# ZenithController.net
KiCad netlist of a schematic drawn in EAGLE
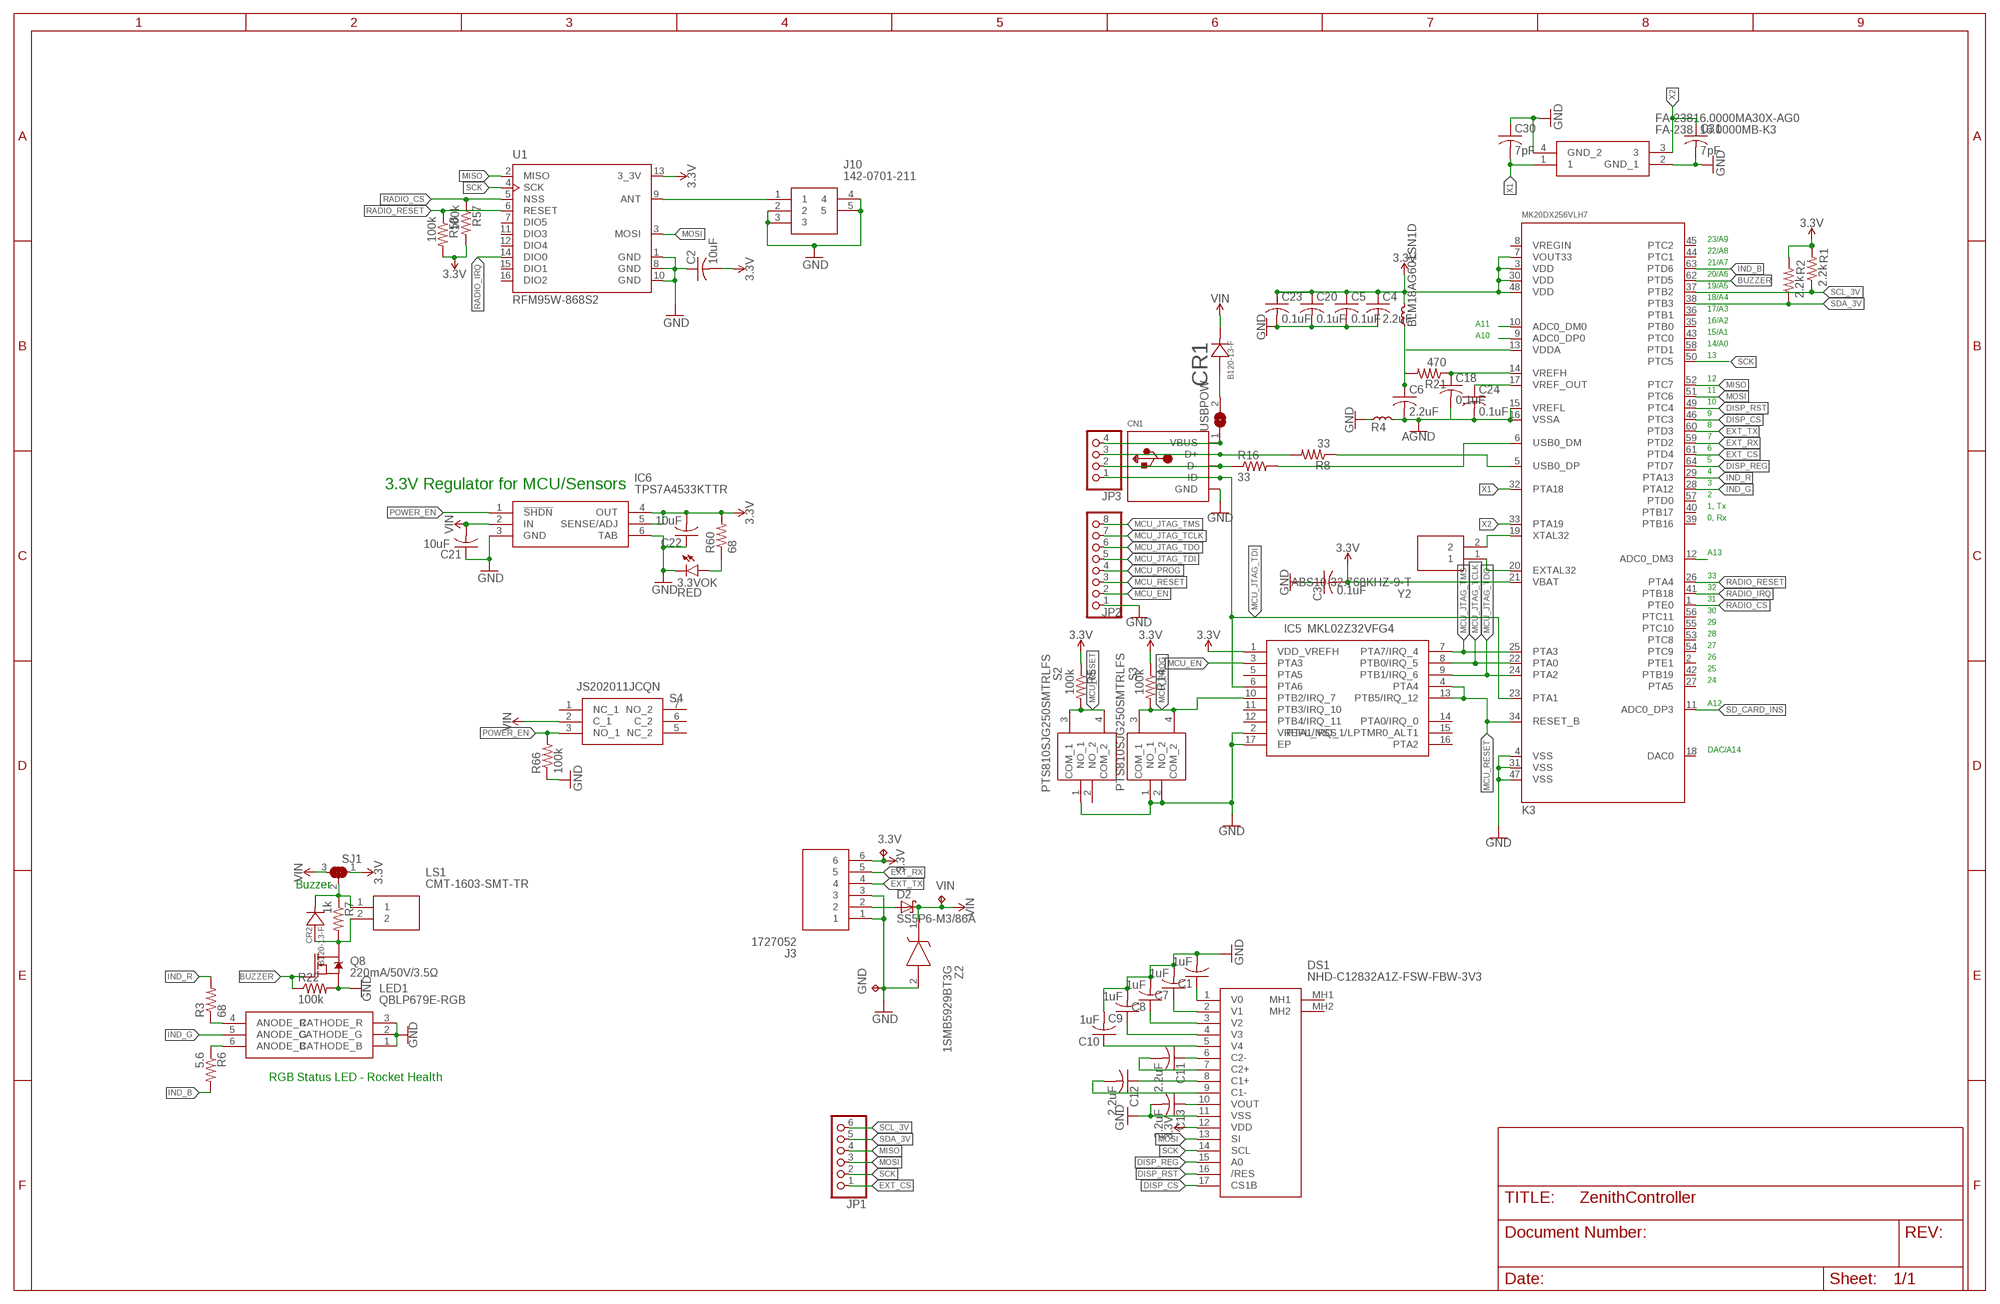
[diagram p0: schematic, sheet 1]

(export (version "E")
  (design (tool "Eeschema 10.0.6"))
  (components
    (comp (ref "3.3V")
      (value "TPB1,27")
      (footprint "eagle-import:B1,27")
      (libsource (lib "eagle-import") (part "TPB1,27"))
    )
    (comp (ref "3.3VOK")
      (value "RED")
      (footprint "eagle-import:CHIP-LED0805")
      (libsource (lib "eagle-import") (part "LEDCHIP-LED0805"))
    )
    (comp (ref "BLM18AG601SN1D")
      (value "FERRITE")
      (footprint "eagle-import:L0603")
      (fields (field (name "MF") "Murata Electronics") (field (name "MPN") " BLM18AG601SN1D"))
      (libsource (lib "eagle-import") (part "FERRITE"))
    )
    (comp (ref "C1")
      (value "1uF")
      (footprint "eagle-import:C0603")
      (libsource (lib "eagle-import") (part "C-USC0603"))
    )
    (comp (ref "C2")
      (value "10uF")
      (footprint "eagle-import:C0603")
      (libsource (lib "eagle-import") (part "C-USC0603"))
    )
    (comp (ref "C3")
      (value "0.1uF")
      (footprint "eagle-import:C0603")
      (libsource (lib "eagle-import") (part "C-USC0603"))
    )
    (comp (ref "C4")
      (value "2.2uF")
      (footprint "eagle-import:C0603")
      (libsource (lib "eagle-import") (part "C-USC0603"))
    )
    (comp (ref "C5")
      (value "0.1uF")
      (footprint "eagle-import:C0603")
      (libsource (lib "eagle-import") (part "C-USC0603"))
    )
    (comp (ref "C6")
      (value "2.2uF")
      (footprint "eagle-import:C0603")
      (libsource (lib "eagle-import") (part "C-USC0603"))
    )
    (comp (ref "C7")
      (value "1uF")
      (footprint "eagle-import:C0603")
      (libsource (lib "eagle-import") (part "C-USC0603"))
    )
    (comp (ref "C8")
      (value "1uF")
      (footprint "eagle-import:C0603")
      (libsource (lib "eagle-import") (part "C-USC0603"))
    )
    (comp (ref "C9")
      (value "1uF")
      (footprint "eagle-import:C0603")
      (libsource (lib "eagle-import") (part "C-USC0603"))
    )
    (comp (ref "C10")
      (value "1uF")
      (footprint "eagle-import:C0603")
      (libsource (lib "eagle-import") (part "C-USC0603"))
    )
    (comp (ref "C11")
      (value "2.2uF")
      (footprint "eagle-import:C0603")
      (libsource (lib "eagle-import") (part "C-USC0603"))
    )
    (comp (ref "C12")
      (value "2.2uF")
      (footprint "eagle-import:C0603")
      (libsource (lib "eagle-import") (part "C-USC0603"))
    )
    (comp (ref "C13")
      (value "2.2uF")
      (footprint "eagle-import:C0603")
      (libsource (lib "eagle-import") (part "C-USC0603"))
    )
    (comp (ref "C18")
      (value "0.1uF")
      (footprint "eagle-import:C0603")
      (libsource (lib "eagle-import") (part "C-USC0603"))
    )
    (comp (ref "C20")
      (value "0.1uF")
      (footprint "eagle-import:C0603")
      (libsource (lib "eagle-import") (part "C-USC0603"))
    )
    (comp (ref "C21")
      (value "10uF")
      (footprint "eagle-import:C0603")
      (libsource (lib "eagle-import") (part "C-USC0603"))
    )
    (comp (ref "C22")
      (value "10uF")
      (footprint "eagle-import:C0603")
      (libsource (lib "eagle-import") (part "C-USC0603"))
    )
    (comp (ref "C23")
      (value "0.1uF")
      (footprint "eagle-import:C0603")
      (libsource (lib "eagle-import") (part "C-USC0603"))
    )
    (comp (ref "C24")
      (value "0.1uF")
      (footprint "eagle-import:C0603")
      (libsource (lib "eagle-import") (part "C-USC0603"))
    )
    (comp (ref "C30")
      (value "7pF")
      (footprint "eagle-import:C0603")
      (libsource (lib "eagle-import") (part "C-USC0603"))
    )
    (comp (ref "C31")
      (value "7pF")
      (footprint "eagle-import:C0603")
      (libsource (lib "eagle-import") (part "C-USC0603"))
    )
    (comp (ref "CN1")
      (value "USBMINIB")
      (footprint "eagle-import:USB-MINIB")
      (libsource (lib "eagle-import") (part "USBMINIB"))
    )
    (comp (ref "CR1")
      (value "B120-13-F")
      (footprint "eagle-import:SMA_DIO")
      (libsource (lib "eagle-import") (part "B120-13-F"))
    )
    (comp (ref "CR2")
      (value "B120-13-F")
      (footprint "eagle-import:SMA_DIO")
      (libsource (lib "eagle-import") (part "B120-13-F"))
    )
    (comp (ref "D2")
      (value "SS5P6-M3/86A")
      (footprint "eagle-import:TO-277A(SMPC)")
      (fields (field (name "MF") "Vishay Semiconductor"))
      (libsource (lib "eagle-import") (part "SS5P6-M3/86A"))
    )
    (comp (ref "DS1")
      (value "NHD-C12832A1Z-FSW-FBW-3V3")
      (footprint "eagle-import:NHDC12832A1ZFSWFBW3V3")
      (fields (field (name "MOUSER_PART_NUMBER") "763-C12832A1ZFSWFBW3"))
      (libsource (lib "eagle-import") (part "NHD-C12832A1Z-FSW-FBW-3V3"))
    )
    (comp (ref "FA-23816.0000MA30X-AG0")
      (value "FA-238_16.0000MB-K3")
      (footprint "eagle-import:EPSON-FA-238")
      (fields
        (field (name "ARROW_PART_NUMBER") "FA-238 16.0000MB-K3")
        (field (name "MOUSER_PART_NUMBER") "732-FA238-16B-K3")
      )
      (libsource (lib "eagle-import") (part "FA-238_16.0000MB-K3"))
    )
    (comp (ref "GND")
      (value "TPB1,27")
      (footprint "eagle-import:B1,27")
      (libsource (lib "eagle-import") (part "TPB1,27"))
    )
    (comp (ref "IC5")
      (value "MKL02Z32VFG4")
      (footprint "eagle-import:QFN50P300X300X65-17N")
      (fields (field (name "MOUSER_PART_NUMBER") "841-MKL02Z32VFG4"))
      (libsource (lib "eagle-import") (part "MKL02Z32VFG4"))
    )
    (comp (ref "IC6")
      (value "TPS7A4533KTTR")
      (footprint "eagle-import:KTT0005B")
      (fields (field (name "MOUSER_PART_NUMBER") "595-TPS7A4533KTTR"))
      (libsource (lib "eagle-import") (part "TPS7A4533KTTR"))
    )
    (comp (ref "J3")
      (value "1727052")
      (footprint "eagle-import:SHDR6W105P0X381_1X6_2285X730X8")
      (fields (field (name "MOUSER_PART_NUMBER") "651-1727052"))
      (libsource (lib "eagle-import") (part "1727052"))
    )
    (comp (ref "J10")
      (value "142-0701-211")
      (footprint "eagle-import:1420701211")
      (fields (field (name "MOUSER_PART_NUMBER") "530-1420701211"))
      (libsource (lib "eagle-import") (part "142-0701-211"))
    )
    (comp (ref "JP1")
      (value "PINHD-1X6")
      (footprint "eagle-import:1X06")
      (libsource (lib "eagle-import") (part "PINHD-1X6"))
    )
    (comp (ref "JP2")
      (value "PINHD-1X8")
      (footprint "eagle-import:1X08")
      (libsource (lib "eagle-import") (part "PINHD-1X8"))
    )
    (comp (ref "JP3")
      (value "PINHD-1X4")
      (footprint "eagle-import:1X04")
      (libsource (lib "eagle-import") (part "PINHD-1X4"))
    )
    (comp (ref "K3")
      (value "MK20DX256VLH7")
      (footprint "eagle-import:LQFP64-05")
      (fields (field (name "MF") "NXP"))
      (libsource (lib "eagle-import") (part "MK20DX256VLH7"))
    )
    (comp (ref "LED1")
      (value "QBLP679E-RGB")
      (footprint "eagle-import:QBLP679ERGB")
      (libsource (lib "eagle-import") (part "QBLP679E-RGB"))
    )
    (comp (ref "LS1")
      (value "CMT-1603-SMT-TR")
      (footprint "eagle-import:CMT1603SMTTR")
      (fields (field (name "MOUSER_PART_NUMBER") "490-CMT-1603-SMT-TR"))
      (libsource (lib "eagle-import") (part "CMT-1603-SMT-TR"))
    )
    (comp (ref "Q8")
      (value "220mA/50V/3.5Ω")
      (footprint "eagle-import:SOT23-3")
      (libsource (lib "eagle-import") (part "MOSFET-NCH-BSS138"))
    )
    (comp (ref "R1")
      (value "2.2k")
      (footprint "eagle-import:R0603")
      (libsource (lib "eagle-import") (part "R-US_R0603"))
    )
    (comp (ref "R2")
      (value "2.2k")
      (footprint "eagle-import:R0603")
      (libsource (lib "eagle-import") (part "R-US_R0603"))
    )
    (comp (ref "R3")
      (value "68")
      (footprint "eagle-import:R0603")
      (libsource (lib "eagle-import") (part "R-US_R0603"))
    )
    (comp (ref "R4")
      (value "FERRITE")
      (footprint "eagle-import:L0603")
      (fields (field (name "MF") "Murata Electronics") (field (name "MPN") " BLM18AG601SN1D"))
      (libsource (lib "eagle-import") (part "FERRITE"))
    )
    (comp (ref "R5")
      (value "100k")
      (footprint "eagle-import:R0603")
      (libsource (lib "eagle-import") (part "R-US_R0603"))
    )
    (comp (ref "R6")
      (value "5.6")
      (footprint "eagle-import:R0603")
      (libsource (lib "eagle-import") (part "R-US_R0603"))
    )
    (comp (ref "R7")
      (value "1k")
      (footprint "eagle-import:R0603")
      (libsource (lib "eagle-import") (part "R-US_R0603"))
    )
    (comp (ref "R8")
      (value "33")
      (footprint "eagle-import:R0603")
      (libsource (lib "eagle-import") (part "R-US_R0603"))
    )
    (comp (ref "R14")
      (value "100k")
      (footprint "eagle-import:R0603")
      (libsource (lib "eagle-import") (part "R-US_R0603"))
    )
    (comp (ref "R16")
      (value "33")
      (footprint "eagle-import:R0603")
      (libsource (lib "eagle-import") (part "R-US_R0603"))
    )
    (comp (ref "R21")
      (value "470")
      (footprint "eagle-import:R0603")
      (libsource (lib "eagle-import") (part "R-US_R0603"))
    )
    (comp (ref "R22")
      (value "100k")
      (footprint "eagle-import:R0603")
      (libsource (lib "eagle-import") (part "R-US_R0603"))
    )
    (comp (ref "R57")
      (value "100k")
      (footprint "eagle-import:R0603")
      (libsource (lib "eagle-import") (part "R-US_R0603"))
    )
    (comp (ref "R58")
      (value "100k")
      (footprint "eagle-import:R0603")
      (libsource (lib "eagle-import") (part "R-US_R0603"))
    )
    (comp (ref "R60")
      (value "68")
      (footprint "eagle-import:R0603")
      (libsource (lib "eagle-import") (part "R-US_R0603"))
    )
    (comp (ref "R66")
      (value "100k")
      (footprint "eagle-import:R0603")
      (libsource (lib "eagle-import") (part "R-US_R0603"))
    )
    (comp (ref "S2")
      (value "PTS810SJG250SMTRLFS")
      (footprint "eagle-import:PTS810SJG250SMTRLFS")
      (fields (field (name "MOUSER_PART_NUMBER") "611-PTS810SJG250SMTR"))
      (libsource (lib "eagle-import") (part "PTS810SJG250SMTRLFS"))
    )
    (comp (ref "S3")
      (value "PTS810SJG250SMTRLFS")
      (footprint "eagle-import:PTS810SJG250SMTRLFS")
      (fields (field (name "MOUSER_PART_NUMBER") "611-PTS810SJG250SMTR"))
      (libsource (lib "eagle-import") (part "PTS810SJG250SMTRLFS"))
    )
    (comp (ref "S4")
      (value "JS202011JCQN")
      (footprint "eagle-import:JS202011JCQN")
      (fields (field (name "MOUSER_PART_NUMBER") "611-JS202011JCQN"))
      (libsource (lib "eagle-import") (part "JS202011JCQN"))
    )
    (comp (ref "SJ1")
      (value "SOLDERJUMPER_2WAY0603")
      (footprint "eagle-import:SOLDERJUMPER_2WAY_OPEN_0603")
      (libsource (lib "eagle-import") (part "SOLDERJUMPER_2WAY0603"))
    )
    (comp (ref "U1")
      (value "RFM95W-868S2")
      (footprint "eagle-import:XCVR_RFM95W-868S2")
      (fields (field (name "MF") "RF"))
      (libsource (lib "eagle-import") (part "RFM95W-868S2"))
    )
    (comp (ref "USBPOW")
      (value "SJ")
      (footprint "eagle-import:SJ")
      (libsource (lib "eagle-import") (part "SJ"))
    )
    (comp (ref "VIN")
      (value "TPB1,27")
      (footprint "eagle-import:B1,27")
      (libsource (lib "eagle-import") (part "TPB1,27"))
    )
    (comp (ref "Y2")
      (value "ABS10-32.768KHZ-9-T")
      (footprint "eagle-import:ABS-10")
      (fields (field (name "MOUSER_PART_NUMBER") "815-ABS10-32.768K9T"))
      (libsource (lib "eagle-import") (part "ABS10-32.768KHZ-9-T"))
    )
    (comp (ref "Z2")
      (value "1SMB5929BT3G")
      (footprint "eagle-import:DIOM5436X247N")
      (fields (field (name "MOUSER_PART_NUMBER") "863-1SMB5929BT3G"))
      (libsource (lib "eagle-import") (part "1SMB5929BT3G"))
    )
  )
  (nets
    (net (code "1") (name "3.3V") (class "Default")
      (node (ref "3.3V") (pin "TP") (pinfunction "TP_TP") (pintype "input"))
      (node (ref "BLM18AG601SN1D") (pin "2") (pinfunction "2_2") (pintype "passive"))
      (node (ref "C2") (pin "2") (pinfunction "2_2") (pintype "passive"))
      (node (ref "C20") (pin "1") (pinfunction "1_1") (pintype "passive"))
      (node (ref "C22") (pin "2") (pinfunction "2_2") (pintype "passive"))
      (node (ref "C23") (pin "1") (pinfunction "1_1") (pintype "passive"))
      (node (ref "C3") (pin "2") (pinfunction "2_2") (pintype "passive"))
      (node (ref "C4") (pin "1") (pinfunction "1_1") (pintype "passive"))
      (node (ref "C5") (pin "1") (pinfunction "1_1") (pintype "passive"))
      (node (ref "DS1") (pin "12") (pinfunction "VDD_12") (pintype "bidirectional"))
      (node (ref "IC5") (pin "1") (pinfunction "VDD_VREFH_1") (pintype "bidirectional"))
      (node (ref "IC6") (pin "4") (pinfunction "OUT_4") (pintype "bidirectional"))
      (node (ref "IC6") (pin "5") (pinfunction "SENSE/ADJ_5") (pintype "bidirectional"))
      (node (ref "J3") (pin "6") (pinfunction "6_6") (pintype "bidirectional"))
      (node (ref "K3") (pin "21") (pinfunction "VBAT_21") (pintype "bidirectional"))
      (node (ref "K3") (pin "3") (pinfunction "VDD_3") (pintype "bidirectional"))
      (node (ref "K3") (pin "30") (pinfunction "VDD_30") (pintype "bidirectional"))
      (node (ref "K3") (pin "48") (pinfunction "VDD_48") (pintype "bidirectional"))
      (node (ref "K3") (pin "7") (pinfunction "VOUT33_7") (pintype "bidirectional"))
      (node (ref "R1") (pin "2") (pinfunction "2_2") (pintype "passive"))
      (node (ref "R14") (pin "1") (pinfunction "1_1") (pintype "passive"))
      (node (ref "R2") (pin "2") (pinfunction "2_2") (pintype "passive"))
      (node (ref "R5") (pin "1") (pinfunction "1_1") (pintype "passive"))
      (node (ref "R57") (pin "2") (pinfunction "2_2") (pintype "passive"))
      (node (ref "R58") (pin "2") (pinfunction "2_2") (pintype "passive"))
      (node (ref "R60") (pin "2") (pinfunction "2_2") (pintype "passive"))
      (node (ref "SJ1") (pin "1") (pinfunction "1_1") (pintype "passive"))
      (node (ref "U1") (pin "13") (pinfunction "3_3V_13") (pintype "power_in"))
    )
    (net (code "2") (name "AGND") (class "Default")
      (node (ref "C18") (pin "2") (pinfunction "2_2") (pintype "passive"))
      (node (ref "C24") (pin "2") (pinfunction "2_2") (pintype "passive"))
      (node (ref "C6") (pin "2") (pinfunction "2_2") (pintype "passive"))
      (node (ref "K3") (pin "15") (pinfunction "VREFL_15") (pintype "bidirectional"))
      (node (ref "K3") (pin "16") (pinfunction "VSSA_16") (pintype "bidirectional"))
      (node (ref "R4") (pin "2") (pinfunction "2_2") (pintype "passive"))
    )
    (net (code "3") (name "BUZZER") (class "Default")
      (node (ref "K3") (pin "62") (pinfunction "PTD5_62") (pintype "bidirectional"))
      (node (ref "Q8") (pin "1") (pinfunction "G_1") (pintype "bidirectional"))
      (node (ref "R22") (pin "1") (pinfunction "1_1") (pintype "passive"))
    )
    (net (code "4") (name "DISP_CS") (class "Default")
      (node (ref "DS1") (pin "17") (pinfunction "CS1B_17") (pintype "bidirectional"))
      (node (ref "K3") (pin "46") (pinfunction "PTC3_46") (pintype "bidirectional"))
    )
    (net (code "5") (name "DISP_REG") (class "Default")
      (node (ref "DS1") (pin "15") (pinfunction "A0_15") (pintype "bidirectional"))
      (node (ref "K3") (pin "64") (pinfunction "PTD7_64") (pintype "bidirectional"))
    )
    (net (code "6") (name "DISP_RST") (class "Default")
      (node (ref "DS1") (pin "16") (pinfunction "/RES_16") (pintype "bidirectional"))
      (node (ref "K3") (pin "49") (pinfunction "PTC4_49") (pintype "bidirectional"))
    )
    (net (code "7") (name "EXT_CS") (class "Default")
      (node (ref "JP1") (pin "1") (pinfunction "1_1") (pintype "passive"))
      (node (ref "K3") (pin "61") (pinfunction "PTD4_61") (pintype "bidirectional"))
    )
    (net (code "8") (name "EXT_RX") (class "Default")
      (node (ref "J3") (pin "5") (pinfunction "5_5") (pintype "bidirectional"))
      (node (ref "K3") (pin "59") (pinfunction "PTD2_59") (pintype "bidirectional"))
    )
    (net (code "9") (name "EXT_TX") (class "Default")
      (node (ref "J3") (pin "4") (pinfunction "4_4") (pintype "bidirectional"))
      (node (ref "K3") (pin "60") (pinfunction "PTD3_60") (pintype "bidirectional"))
    )
    (net (code "10") (name "GND") (class "Default")
      (node (ref "3.3VOK") (pin "C") (pinfunction "C_C") (pintype "passive"))
      (node (ref "C1") (pin "2") (pinfunction "2_2") (pintype "passive"))
      (node (ref "C10") (pin "2") (pinfunction "2_2") (pintype "passive"))
      (node (ref "C13") (pin "2") (pinfunction "2_2") (pintype "passive"))
      (node (ref "C2") (pin "1") (pinfunction "1_1") (pintype "passive"))
      (node (ref "C20") (pin "2") (pinfunction "2_2") (pintype "passive"))
      (node (ref "C21") (pin "1") (pinfunction "1_1") (pintype "passive"))
      (node (ref "C22") (pin "1") (pinfunction "1_1") (pintype "passive"))
      (node (ref "C23") (pin "2") (pinfunction "2_2") (pintype "passive"))
      (node (ref "C3") (pin "1") (pinfunction "1_1") (pintype "passive"))
      (node (ref "C30") (pin "1") (pinfunction "1_1") (pintype "passive"))
      (node (ref "C31") (pin "2") (pinfunction "2_2") (pintype "passive"))
      (node (ref "C4") (pin "2") (pinfunction "2_2") (pintype "passive"))
      (node (ref "C5") (pin "2") (pinfunction "2_2") (pintype "passive"))
      (node (ref "C7") (pin "2") (pinfunction "2_2") (pintype "passive"))
      (node (ref "C8") (pin "2") (pinfunction "2_2") (pintype "passive"))
      (node (ref "C9") (pin "2") (pinfunction "2_2") (pintype "passive"))
      (node (ref "CN1") (pin "GND") (pinfunction "GND_GND") (pintype "power_in"))
      (node (ref "DS1") (pin "11") (pinfunction "VSS_11") (pintype "bidirectional"))
      (node (ref "FA-23816.0000MA30X-AG0") (pin "2") (pinfunction "GND_1_2") (pintype "power_in"))
      (node (ref "FA-23816.0000MA30X-AG0") (pin "4") (pinfunction "GND_2_4") (pintype "power_in"))
      (node (ref "GND") (pin "TP") (pinfunction "TP_TP") (pintype "input"))
      (node (ref "IC5") (pin "17") (pinfunction "EP_17") (pintype "bidirectional"))
      (node (ref "IC5") (pin "2") (pinfunction "VREFL_VSS_2") (pintype "bidirectional"))
      (node (ref "IC6") (pin "3") (pinfunction "GND_3") (pintype "bidirectional"))
      (node (ref "IC6") (pin "6") (pinfunction "TAB_6") (pintype "bidirectional"))
      (node (ref "J10") (pin "2") (pinfunction "2_2") (pintype "bidirectional"))
      (node (ref "J10") (pin "3") (pinfunction "3_3") (pintype "bidirectional"))
      (node (ref "J10") (pin "4") (pinfunction "4_4") (pintype "bidirectional"))
      (node (ref "J10") (pin "5") (pinfunction "5_5") (pintype "bidirectional"))
      (node (ref "J3") (pin "1") (pinfunction "1_1") (pintype "bidirectional"))
      (node (ref "J3") (pin "3") (pinfunction "3_3") (pintype "bidirectional"))
      (node (ref "JP2") (pin "1") (pinfunction "1_1") (pintype "passive"))
      (node (ref "K3") (pin "31") (pinfunction "VSS_31") (pintype "bidirectional"))
      (node (ref "K3") (pin "4") (pinfunction "VSS_4") (pintype "bidirectional"))
      (node (ref "K3") (pin "47") (pinfunction "VSS_47") (pintype "bidirectional"))
      (node (ref "LED1") (pin "1") (pinfunction "CATHODE_B_1") (pintype "bidirectional"))
      (node (ref "LED1") (pin "2") (pinfunction "CATHODE_G_2") (pintype "bidirectional"))
      (node (ref "LED1") (pin "3") (pinfunction "CATHODE_R_3") (pintype "bidirectional"))
      (node (ref "Q8") (pin "2") (pinfunction "S_2") (pintype "bidirectional"))
      (node (ref "R22") (pin "2") (pinfunction "2_2") (pintype "passive"))
      (node (ref "R4") (pin "1") (pinfunction "1_1") (pintype "passive"))
      (node (ref "R66") (pin "1") (pinfunction "1_1") (pintype "passive"))
      (node (ref "S2") (pin "1") (pinfunction "NO_1_1") (pintype "bidirectional"))
      (node (ref "S3") (pin "1") (pinfunction "NO_1_1") (pintype "bidirectional"))
      (node (ref "S3") (pin "2") (pinfunction "NO_2_2") (pintype "bidirectional"))
      (node (ref "U1") (pin "1") (pinfunction "GND_1") (pintype "power_in"))
      (node (ref "U1") (pin "10") (pinfunction "GND_10") (pintype "power_in"))
      (node (ref "U1") (pin "8") (pinfunction "GND_8") (pintype "power_in"))
      (node (ref "Z2") (pin "2") (pinfunction "A_2") (pintype "bidirectional"))
    )
    (net (code "11") (name "IND_B") (class "Default")
      (node (ref "K3") (pin "63") (pinfunction "PTD6_63") (pintype "bidirectional"))
      (node (ref "R6") (pin "2") (pinfunction "2_2") (pintype "passive"))
    )
    (net (code "12") (name "IND_G") (class "Default")
      (node (ref "K3") (pin "28") (pinfunction "PTA12_28") (pintype "bidirectional"))
      (node (ref "LED1") (pin "5") (pinfunction "ANODE_G_5") (pintype "bidirectional"))
    )
    (net (code "13") (name "IND_R") (class "Default")
      (node (ref "K3") (pin "29") (pinfunction "PTA13_29") (pintype "bidirectional"))
      (node (ref "R3") (pin "2") (pinfunction "2_2") (pintype "passive"))
    )
    (net (code "14") (name "MCU_EN") (class "Default")
      (node (ref "IC5") (pin "3") (pinfunction "PTA3_3") (pintype "bidirectional"))
      (node (ref "JP2") (pin "2") (pinfunction "2_2") (pintype "passive"))
    )
    (net (code "15") (name "MCU_JTAG_TCLK") (class "Default")
      (node (ref "IC5") (pin "8") (pinfunction "PTB0/IRQ_5_8") (pintype "bidirectional"))
      (node (ref "JP2") (pin "7") (pinfunction "7_7") (pintype "passive"))
      (node (ref "K3") (pin "22") (pinfunction "PTA0_22") (pintype "bidirectional"))
    )
    (net (code "16") (name "MCU_JTAG_TDI") (class "Default")
      (node (ref "CN1") (pin "ID") (pinfunction "ID_ID") (pintype "bidirectional"))
      (node (ref "IC5") (pin "6") (pinfunction "PTA6_6") (pintype "bidirectional"))
      (node (ref "JP2") (pin "5") (pinfunction "5_5") (pintype "passive"))
      (node (ref "JP3") (pin "1") (pinfunction "1_1") (pintype "passive"))
      (node (ref "K3") (pin "23") (pinfunction "PTA1_23") (pintype "bidirectional"))
    )
    (net (code "17") (name "MCU_JTAG_TDO") (class "Default")
      (node (ref "IC5") (pin "9") (pinfunction "PTB1/IRQ_6_9") (pintype "bidirectional"))
      (node (ref "JP2") (pin "6") (pinfunction "6_6") (pintype "passive"))
      (node (ref "K3") (pin "24") (pinfunction "PTA2_24") (pintype "bidirectional"))
    )
    (net (code "18") (name "MCU_JTAG_TMS") (class "Default")
      (node (ref "IC5") (pin "7") (pinfunction "PTA7/IRQ_4_7") (pintype "bidirectional"))
      (node (ref "JP2") (pin "8") (pinfunction "8_8") (pintype "passive"))
      (node (ref "K3") (pin "25") (pinfunction "PTA3_25") (pintype "bidirectional"))
    )
    (net (code "19") (name "MCU_PROG") (class "Default")
      (node (ref "IC5") (pin "10") (pinfunction "PTB2/IRQ_7_10") (pintype "bidirectional"))
      (node (ref "JP2") (pin "4") (pinfunction "4_4") (pintype "passive"))
      (node (ref "R14") (pin "2") (pinfunction "2_2") (pintype "passive"))
      (node (ref "S3") (pin "3") (pinfunction "COM_1_3") (pintype "bidirectional"))
      (node (ref "S3") (pin "4") (pinfunction "COM_2_4") (pintype "bidirectional"))
    )
    (net (code "20") (name "MCU_RESET") (class "Default")
      (node (ref "IC5") (pin "13") (pinfunction "PTB5/IRQ_12_13") (pintype "bidirectional"))
      (node (ref "IC5") (pin "4") (pinfunction "PTA4_4") (pintype "bidirectional"))
      (node (ref "JP2") (pin "3") (pinfunction "3_3") (pintype "passive"))
      (node (ref "K3") (pin "34") (pinfunction "RESET_B_34") (pintype "bidirectional"))
      (node (ref "R5") (pin "2") (pinfunction "2_2") (pintype "passive"))
      (node (ref "S2") (pin "3") (pinfunction "COM_1_3") (pintype "bidirectional"))
      (node (ref "S2") (pin "4") (pinfunction "COM_2_4") (pintype "bidirectional"))
    )
    (net (code "21") (name "MISO") (class "Default")
      (node (ref "JP1") (pin "4") (pinfunction "4_4") (pintype "passive"))
      (node (ref "K3") (pin "52") (pinfunction "PTC7_52") (pintype "bidirectional"))
      (node (ref "U1") (pin "2") (pinfunction "MISO_2") (pintype "input"))
    )
    (net (code "22") (name "MOSI") (class "Default")
      (node (ref "DS1") (pin "13") (pinfunction "SI_13") (pintype "bidirectional"))
      (node (ref "JP1") (pin "3") (pinfunction "3_3") (pintype "passive"))
      (node (ref "K3") (pin "51") (pinfunction "PTC6_51") (pintype "bidirectional"))
      (node (ref "U1") (pin "3") (pinfunction "MOSI_3") (pintype "output"))
    )
    (net (code "23") (name "Net-(3.3VOK-PadA)") (class "Default")
      (node (ref "3.3VOK") (pin "A") (pinfunction "A_A") (pintype "passive"))
      (node (ref "R60") (pin "1") (pinfunction "1_1") (pintype "passive"))
    )
    (net (code "24") (name "Net-(BLM18AG601SN1D-Pad1)") (class "Default")
      (node (ref "BLM18AG601SN1D") (pin "1") (pinfunction "1_1") (pintype "passive"))
      (node (ref "C6") (pin "1") (pinfunction "1_1") (pintype "passive"))
      (node (ref "R21") (pin "2") (pinfunction "2_2") (pintype "passive"))
    )
    (net (code "25") (name "Net-(CN1-PadD+)") (class "Default")
      (node (ref "CN1") (pin "D+") (pinfunction "D+_D+") (pintype "bidirectional"))
      (node (ref "JP3") (pin "3") (pinfunction "3_3") (pintype "passive"))
      (node (ref "R8") (pin "2") (pinfunction "2_2") (pintype "passive"))
    )
    (net (code "26") (name "Net-(CN1-PadD-)") (class "Default")
      (node (ref "CN1") (pin "D-") (pinfunction "D-_D-") (pintype "bidirectional"))
      (node (ref "JP3") (pin "2") (pinfunction "2_2") (pintype "passive"))
      (node (ref "R16") (pin "1") (pinfunction "1_1") (pintype "passive"))
    )
    (net (code "27") (name "Net-(CN1-PadVBUS)") (class "Default")
      (node (ref "CN1") (pin "VBUS") (pinfunction "VBUS_VBUS") (pintype "power_in"))
      (node (ref "JP3") (pin "4") (pinfunction "4_4") (pintype "passive"))
      (node (ref "USBPOW") (pin "1") (pinfunction "1_1") (pintype "passive"))
    )
    (net (code "28") (name "Net-(CR1-Pad2)") (class "Default")
      (node (ref "CR1") (pin "2") (pinfunction "2_2") (pintype "passive"))
      (node (ref "USBPOW") (pin "2") (pinfunction "2_2") (pintype "passive"))
    )
    (net (code "29") (name "Net-(CR2-Pad1)") (class "Default")
      (node (ref "CR2") (pin "1") (pinfunction "1_1") (pintype "passive"))
      (node (ref "LS1") (pin "1") (pinfunction "1_1") (pintype "bidirectional"))
      (node (ref "R7") (pin "1") (pinfunction "1_1") (pintype "passive"))
      (node (ref "SJ1") (pin "2") (pinfunction "2_2") (pintype "passive"))
    )
    (net (code "30") (name "Net-(D2-A-PadA1)") (class "Default")
      (node (ref "D2") (pin "A1") (pinfunction "A_A1") (pintype "passive"))
      (node (ref "D2") (pin "A2") (pinfunction "A_A2") (pintype "passive"))
      (node (ref "J3") (pin "2") (pinfunction "2_2") (pintype "bidirectional"))
    )
    (net (code "31") (name "Net-(DS1-C1+)") (class "Default")
      (node (ref "C12") (pin "1") (pinfunction "1_1") (pintype "passive"))
      (node (ref "DS1") (pin "8") (pinfunction "C1+_8") (pintype "bidirectional"))
    )
    (net (code "32") (name "Net-(DS1-C1-)") (class "Default")
      (node (ref "C12") (pin "2") (pinfunction "2_2") (pintype "passive"))
      (node (ref "DS1") (pin "9") (pinfunction "C1-_9") (pintype "bidirectional"))
    )
    (net (code "33") (name "Net-(DS1-C2+)") (class "Default")
      (node (ref "C11") (pin "2") (pinfunction "2_2") (pintype "passive"))
      (node (ref "DS1") (pin "7") (pinfunction "C2+_7") (pintype "bidirectional"))
    )
    (net (code "34") (name "Net-(DS1-C2-)") (class "Default")
      (node (ref "C11") (pin "1") (pinfunction "1_1") (pintype "passive"))
      (node (ref "DS1") (pin "6") (pinfunction "C2-_6") (pintype "bidirectional"))
    )
    (net (code "35") (name "Net-(DS1-V0)") (class "Default")
      (node (ref "C1") (pin "1") (pinfunction "1_1") (pintype "passive"))
      (node (ref "DS1") (pin "1") (pinfunction "V0_1") (pintype "bidirectional"))
    )
    (net (code "36") (name "Net-(DS1-V1)") (class "Default")
      (node (ref "C7") (pin "1") (pinfunction "1_1") (pintype "passive"))
      (node (ref "DS1") (pin "2") (pinfunction "V1_2") (pintype "bidirectional"))
    )
    (net (code "37") (name "Net-(DS1-V2)") (class "Default")
      (node (ref "C8") (pin "1") (pinfunction "1_1") (pintype "passive"))
      (node (ref "DS1") (pin "3") (pinfunction "V2_3") (pintype "bidirectional"))
    )
    (net (code "38") (name "Net-(DS1-V3)") (class "Default")
      (node (ref "C9") (pin "1") (pinfunction "1_1") (pintype "passive"))
      (node (ref "DS1") (pin "4") (pinfunction "V3_4") (pintype "bidirectional"))
    )
    (net (code "39") (name "Net-(DS1-V4)") (class "Default")
      (node (ref "C10") (pin "1") (pinfunction "1_1") (pintype "passive"))
      (node (ref "DS1") (pin "5") (pinfunction "V4_5") (pintype "bidirectional"))
    )
    (net (code "40") (name "Net-(DS1-VOUT)") (class "Default")
      (node (ref "C13") (pin "1") (pinfunction "1_1") (pintype "passive"))
      (node (ref "DS1") (pin "10") (pinfunction "VOUT_10") (pintype "bidirectional"))
    )
    (net (code "41") (name "Net-(K3-EXTAL32)") (class "Default")
      (node (ref "K3") (pin "20") (pinfunction "EXTAL32_20") (pintype "bidirectional"))
      (node (ref "Y2") (pin "1") (pinfunction "1_1") (pintype "bidirectional"))
    )
    (net (code "42") (name "Net-(K3-USB0_DM)") (class "Default")
      (node (ref "K3") (pin "6") (pinfunction "USB0_DM_6") (pintype "bidirectional"))
      (node (ref "R16") (pin "2") (pinfunction "2_2") (pintype "passive"))
    )
    (net (code "43") (name "Net-(K3-USB0_DP)") (class "Default")
      (node (ref "K3") (pin "5") (pinfunction "USB0_DP_5") (pintype "bidirectional"))
      (node (ref "R8") (pin "1") (pinfunction "1_1") (pintype "passive"))
    )
    (net (code "44") (name "Net-(K3-VREFH)") (class "Default")
      (node (ref "C18") (pin "1") (pinfunction "1_1") (pintype "passive"))
      (node (ref "K3") (pin "14") (pinfunction "VREFH_14") (pintype "bidirectional"))
      (node (ref "R21") (pin "1") (pinfunction "1_1") (pintype "passive"))
    )
    (net (code "45") (name "Net-(K3-VREF_OUT)") (class "Default")
      (node (ref "C24") (pin "1") (pinfunction "1_1") (pintype "passive"))
      (node (ref "K3") (pin "17") (pinfunction "VREF_OUT_17") (pintype "bidirectional"))
    )
    (net (code "46") (name "Net-(K3-XTAL32)") (class "Default")
      (node (ref "K3") (pin "19") (pinfunction "XTAL32_19") (pintype "bidirectional"))
      (node (ref "Y2") (pin "2") (pinfunction "2_2") (pintype "bidirectional"))
    )
    (net (code "47") (name "Net-(LED1-ANODE_B)") (class "Default")
      (node (ref "LED1") (pin "6") (pinfunction "ANODE_B_6") (pintype "bidirectional"))
      (node (ref "R6") (pin "1") (pinfunction "1_1") (pintype "passive"))
    )
    (net (code "48") (name "Net-(LED1-ANODE_R)") (class "Default")
      (node (ref "LED1") (pin "4") (pinfunction "ANODE_R_4") (pintype "bidirectional"))
      (node (ref "R3") (pin "1") (pinfunction "1_1") (pintype "passive"))
    )
    (net (code "49") (name "Net-(Q8-D)") (class "Default")
      (node (ref "CR2") (pin "2") (pinfunction "2_2") (pintype "passive"))
      (node (ref "LS1") (pin "2") (pinfunction "2_2") (pintype "bidirectional"))
      (node (ref "Q8") (pin "3") (pinfunction "D_3") (pintype "bidirectional"))
      (node (ref "R7") (pin "2") (pinfunction "2_2") (pintype "passive"))
    )
    (net (code "50") (name "Net-(U1-ANT)") (class "Default")
      (node (ref "J10") (pin "1") (pinfunction "1_1") (pintype "bidirectional"))
      (node (ref "U1") (pin "9") (pinfunction "ANT_9") (pintype "passive"))
    )
    (net (code "51") (name "POWER_EN") (class "Default")
      (node (ref "IC6") (pin "1") (pinfunction "~{SHDN}_1") (pintype "bidirectional"))
      (node (ref "R66") (pin "2") (pinfunction "2_2") (pintype "passive"))
      (node (ref "S4") (pin "3") (pinfunction "NO_1_3") (pintype "bidirectional"))
    )
    (net (code "52") (name "RADIO_CS") (class "Default")
      (node (ref "K3") (pin "1") (pinfunction "PTE0_1") (pintype "bidirectional"))
      (node (ref "R57") (pin "1") (pinfunction "1_1") (pintype "passive"))
      (node (ref "U1") (pin "5") (pinfunction "NSS_5") (pintype "input"))
    )
    (net (code "53") (name "RADIO_IRQ") (class "Default")
      (node (ref "K3") (pin "41") (pinfunction "PTB18_41") (pintype "bidirectional"))
      (node (ref "U1") (pin "14") (pinfunction "DIO0_14") (pintype "bidirectional"))
    )
    (net (code "54") (name "RADIO_RESET") (class "Default")
      (node (ref "K3") (pin "26") (pinfunction "PTA4_26") (pintype "bidirectional"))
      (node (ref "R58") (pin "1") (pinfunction "1_1") (pintype "passive"))
      (node (ref "U1") (pin "6") (pinfunction "RESET_6") (pintype "bidirectional"))
    )
    (net (code "55") (name "SCK") (class "Default")
      (node (ref "DS1") (pin "14") (pinfunction "SCL_14") (pintype "bidirectional"))
      (node (ref "JP1") (pin "2") (pinfunction "2_2") (pintype "passive"))
      (node (ref "K3") (pin "50") (pinfunction "PTC5_50") (pintype "bidirectional"))
      (node (ref "U1") (pin "4") (pinfunction "SCK_4") (pintype "input"))
    )
    (net (code "56") (name "SCL_3V") (class "Default")
      (node (ref "JP1") (pin "6") (pinfunction "6_6") (pintype "passive"))
      (node (ref "K3") (pin "37") (pinfunction "PTB2_37") (pintype "bidirectional"))
      (node (ref "R1") (pin "1") (pinfunction "1_1") (pintype "passive"))
    )
    (net (code "57") (name "SDA_3V") (class "Default")
      (node (ref "JP1") (pin "5") (pinfunction "5_5") (pintype "passive"))
      (node (ref "K3") (pin "38") (pinfunction "PTB3_38") (pintype "bidirectional"))
      (node (ref "R2") (pin "1") (pinfunction "1_1") (pintype "passive"))
    )
    (net (code "58") (name "SD_CARD_INS") (class "Default")
      (node (ref "K3") (pin "11") (pinfunction "ADC0_DP3_11") (pintype "bidirectional"))
    )
    (net (code "59") (name "VIN") (class "Default")
      (node (ref "C21") (pin "2") (pinfunction "2_2") (pintype "passive"))
      (node (ref "CR1") (pin "1") (pinfunction "1_1") (pintype "passive"))
      (node (ref "D2") (pin "K") (pinfunction "C_K") (pintype "passive"))
      (node (ref "IC6") (pin "2") (pinfunction "IN_2") (pintype "bidirectional"))
      (node (ref "S4") (pin "2") (pinfunction "C_1_2") (pintype "bidirectional"))
      (node (ref "SJ1") (pin "3") (pinfunction "3_3") (pintype "passive"))
      (node (ref "VIN") (pin "TP") (pinfunction "TP_TP") (pintype "input"))
      (node (ref "Z2") (pin "1") (pinfunction "K_1") (pintype "bidirectional"))
    )
    (net (code "60") (name "X1") (class "Default")
      (node (ref "C30") (pin "2") (pinfunction "2_2") (pintype "passive"))
      (node (ref "FA-23816.0000MA30X-AG0") (pin "1") (pinfunction "1_1") (pintype "bidirectional"))
      (node (ref "K3") (pin "32") (pinfunction "PTA18_32") (pintype "bidirectional"))
    )
    (net (code "61") (name "X2") (class "Default")
      (node (ref "C31") (pin "1") (pinfunction "1_1") (pintype "passive"))
      (node (ref "FA-23816.0000MA30X-AG0") (pin "3") (pinfunction "3_3") (pintype "bidirectional"))
      (node (ref "K3") (pin "33") (pinfunction "PTA19_33") (pintype "bidirectional"))
    )
    (net (code "62") (name "unconnected-(DS1-PadMH1)") (class "Default")
      (node (ref "DS1") (pin "MH1") (pinfunction "MH1_MH1") (pintype "bidirectional"))
    )
    (net (code "63") (name "unconnected-(DS1-PadMH2)") (class "Default")
      (node (ref "DS1") (pin "MH2") (pinfunction "MH2_MH2") (pintype "bidirectional"))
    )
    (net (code "64") (name "unconnected-(IC5-PTA0{slash}IRQ_0-Pad14)") (class "Default")
      (node (ref "IC5") (pin "14") (pinfunction "PTA0/IRQ_0_14") (pintype "bidirectional"))
    )
    (net (code "65") (name "unconnected-(IC5-PTA1{slash}IRQ_1{slash}LPTMR0_ALT1-Pad15)") (class "Default")
      (node (ref "IC5") (pin "15") (pinfunction "PTA1/IRQ_1/LPTMR0_ALT1_15") (pintype "bidirectional"))
    )
    (net (code "66") (name "unconnected-(IC5-PTA2-Pad16)") (class "Default")
      (node (ref "IC5") (pin "16") (pinfunction "PTA2_16") (pintype "bidirectional"))
    )
    (net (code "67") (name "unconnected-(IC5-PTA5-Pad5)") (class "Default")
      (node (ref "IC5") (pin "5") (pinfunction "PTA5_5") (pintype "bidirectional"))
    )
    (net (code "68") (name "unconnected-(IC5-PTB3{slash}IRQ_10-Pad11)") (class "Default")
      (node (ref "IC5") (pin "11") (pinfunction "PTB3/IRQ_10_11") (pintype "bidirectional"))
    )
    (net (code "69") (name "unconnected-(IC5-PTB4{slash}IRQ_11-Pad12)") (class "Default")
      (node (ref "IC5") (pin "12") (pinfunction "PTB4/IRQ_11_12") (pintype "bidirectional"))
    )
    (net (code "70") (name "unconnected-(K3-ADC0_DM0-Pad10)") (class "Default")
      (node (ref "K3") (pin "10") (pinfunction "ADC0_DM0_10") (pintype "bidirectional"))
    )
    (net (code "71") (name "unconnected-(K3-ADC0_DM3-Pad12)") (class "Default")
      (node (ref "K3") (pin "12") (pinfunction "ADC0_DM3_12") (pintype "bidirectional"))
    )
    (net (code "72") (name "unconnected-(K3-ADC0_DP0-Pad9)") (class "Default")
      (node (ref "K3") (pin "9") (pinfunction "ADC0_DP0_9") (pintype "bidirectional"))
    )
    (net (code "73") (name "unconnected-(K3-DAC0-Pad18)") (class "Default")
      (node (ref "K3") (pin "18") (pinfunction "DAC0_18") (pintype "bidirectional"))
    )
    (net (code "74") (name "unconnected-(K3-PTA5-Pad27)") (class "Default")
      (node (ref "K3") (pin "27") (pinfunction "PTA5_27") (pintype "bidirectional"))
    )
    (net (code "75") (name "unconnected-(K3-PTB0-Pad35)") (class "Default")
      (node (ref "K3") (pin "35") (pinfunction "PTB0_35") (pintype "bidirectional"))
    )
    (net (code "76") (name "unconnected-(K3-PTB1-Pad36)") (class "Default")
      (node (ref "K3") (pin "36") (pinfunction "PTB1_36") (pintype "bidirectional"))
    )
    (net (code "77") (name "unconnected-(K3-PTB16-Pad39)") (class "Default")
      (node (ref "K3") (pin "39") (pinfunction "PTB16_39") (pintype "bidirectional"))
    )
    (net (code "78") (name "unconnected-(K3-PTB17-Pad40)") (class "Default")
      (node (ref "K3") (pin "40") (pinfunction "PTB17_40") (pintype "bidirectional"))
    )
    (net (code "79") (name "unconnected-(K3-PTB19-Pad42)") (class "Default")
      (node (ref "K3") (pin "42") (pinfunction "PTB19_42") (pintype "bidirectional"))
    )
    (net (code "80") (name "unconnected-(K3-PTC0-Pad43)") (class "Default")
      (node (ref "K3") (pin "43") (pinfunction "PTC0_43") (pintype "bidirectional"))
    )
    (net (code "81") (name "unconnected-(K3-PTC1-Pad44)") (class "Default")
      (node (ref "K3") (pin "44") (pinfunction "PTC1_44") (pintype "bidirectional"))
    )
    (net (code "82") (name "unconnected-(K3-PTC2-Pad45)") (class "Default")
      (node (ref "K3") (pin "45") (pinfunction "PTC2_45") (pintype "bidirectional"))
    )
    (net (code "83") (name "unconnected-(K3-PTC8-Pad53)") (class "Default")
      (node (ref "K3") (pin "53") (pinfunction "PTC8_53") (pintype "bidirectional"))
    )
    (net (code "84") (name "unconnected-(K3-PTC9-Pad54)") (class "Default")
      (node (ref "K3") (pin "54") (pinfunction "PTC9_54") (pintype "bidirectional"))
    )
    (net (code "85") (name "unconnected-(K3-PTC10-Pad55)") (class "Default")
      (node (ref "K3") (pin "55") (pinfunction "PTC10_55") (pintype "bidirectional"))
    )
    (net (code "86") (name "unconnected-(K3-PTC11-Pad56)") (class "Default")
      (node (ref "K3") (pin "56") (pinfunction "PTC11_56") (pintype "bidirectional"))
    )
    (net (code "87") (name "unconnected-(K3-PTD0-Pad57)") (class "Default")
      (node (ref "K3") (pin "57") (pinfunction "PTD0_57") (pintype "bidirectional"))
    )
    (net (code "88") (name "unconnected-(K3-PTD1-Pad58)") (class "Default")
      (node (ref "K3") (pin "58") (pinfunction "PTD1_58") (pintype "bidirectional"))
    )
    (net (code "89") (name "unconnected-(K3-PTE1-Pad2)") (class "Default")
      (node (ref "K3") (pin "2") (pinfunction "PTE1_2") (pintype "bidirectional"))
    )
    (net (code "90") (name "unconnected-(K3-VDDA-Pad13)") (class "Default")
      (node (ref "K3") (pin "13") (pinfunction "VDDA_13") (pintype "bidirectional"))
    )
    (net (code "91") (name "unconnected-(K3-VREGIN-Pad8)") (class "Default")
      (node (ref "K3") (pin "8") (pinfunction "VREGIN_8") (pintype "bidirectional"))
    )
    (net (code "92") (name "unconnected-(S2-NO_2-Pad2)") (class "Default")
      (node (ref "S2") (pin "2") (pinfunction "NO_2_2") (pintype "bidirectional"))
    )
    (net (code "93") (name "unconnected-(S4-C_2-Pad6)") (class "Default")
      (node (ref "S4") (pin "6") (pinfunction "C_2_6") (pintype "bidirectional"))
    )
    (net (code "94") (name "unconnected-(S4-NC_1-Pad1)") (class "Default")
      (node (ref "S4") (pin "1") (pinfunction "NC_1_1") (pintype "bidirectional"))
    )
    (net (code "95") (name "unconnected-(S4-NC_2-Pad5)") (class "Default")
      (node (ref "S4") (pin "5") (pinfunction "NC_2_5") (pintype "bidirectional"))
    )
    (net (code "96") (name "unconnected-(S4-NO_2-Pad7)") (class "Default")
      (node (ref "S4") (pin "7") (pinfunction "NO_2_7") (pintype "bidirectional"))
    )
    (net (code "97") (name "unconnected-(U1-DIO1-Pad15)") (class "Default")
      (node (ref "U1") (pin "15") (pinfunction "DIO1_15") (pintype "bidirectional"))
    )
    (net (code "98") (name "unconnected-(U1-DIO2-Pad16)") (class "Default")
      (node (ref "U1") (pin "16") (pinfunction "DIO2_16") (pintype "bidirectional"))
    )
    (net (code "99") (name "unconnected-(U1-DIO3-Pad11)") (class "Default")
      (node (ref "U1") (pin "11") (pinfunction "DIO3_11") (pintype "bidirectional"))
    )
    (net (code "100") (name "unconnected-(U1-DIO4-Pad12)") (class "Default")
      (node (ref "U1") (pin "12") (pinfunction "DIO4_12") (pintype "bidirectional"))
    )
    (net (code "101") (name "unconnected-(U1-DIO5-Pad7)") (class "Default")
      (node (ref "U1") (pin "7") (pinfunction "DIO5_7") (pintype "bidirectional"))
    )
  )
)
